# CPU_ROM.net
KiCad netlist of a schematic drawn in Altium Designer
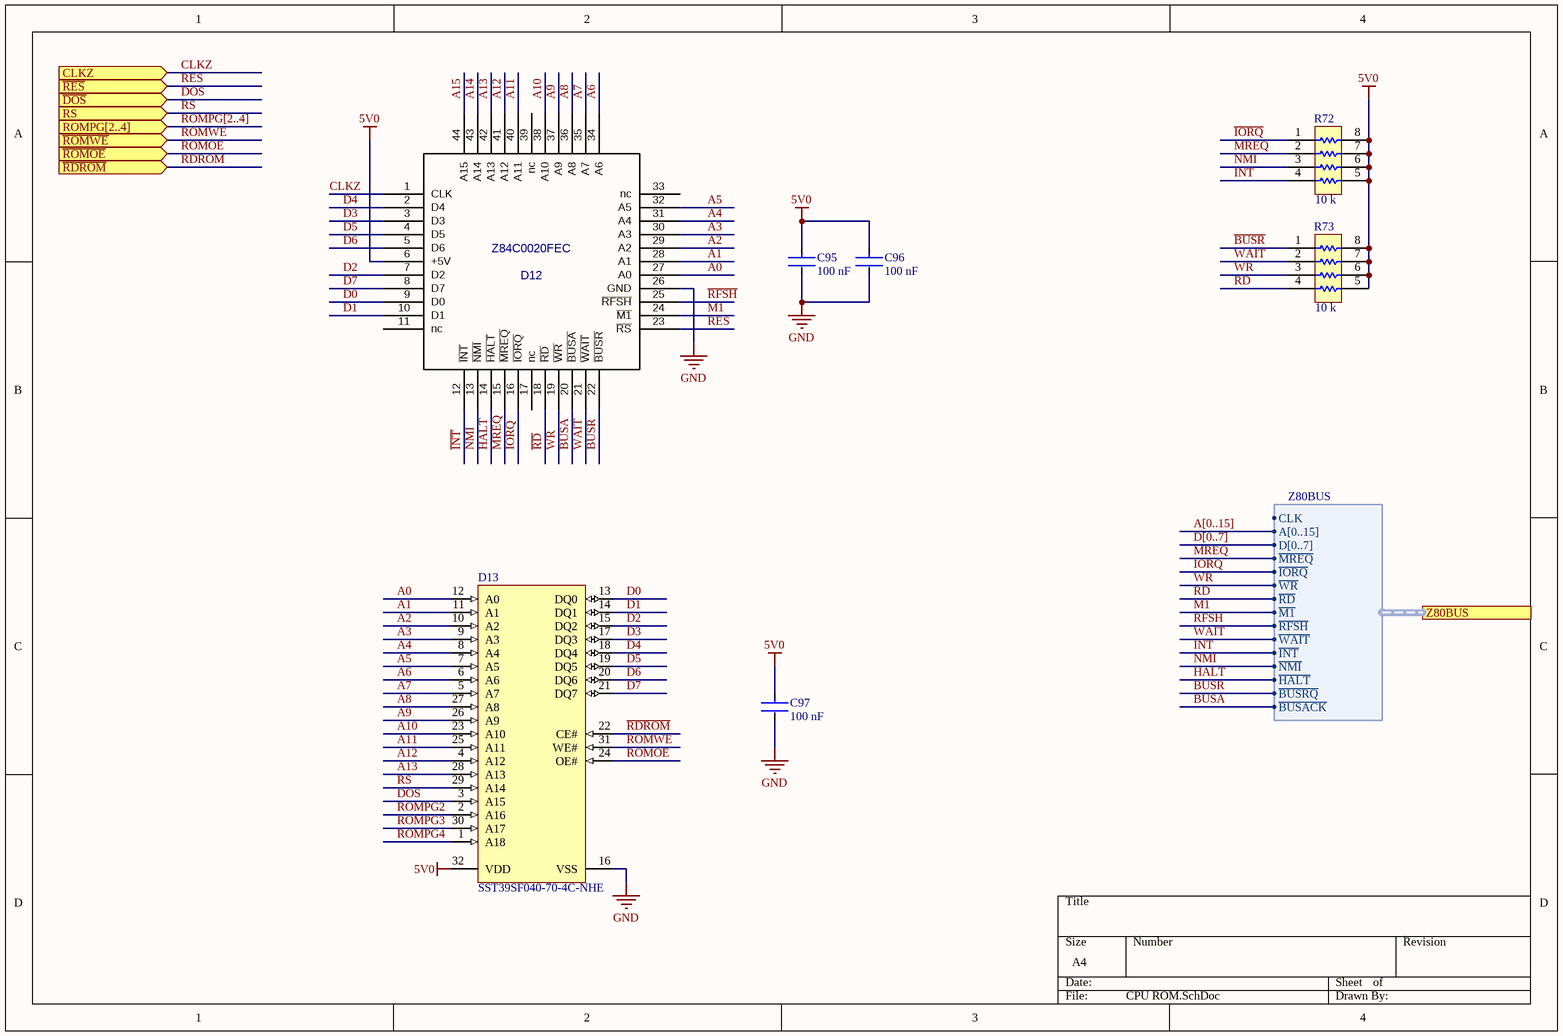
[diagram p0: CPU ROM.SchDoc]

(export (version "E")
  (design (tool "Eeschema 10.0.6"))
  (components
    (comp (ref "C95")
      (value "CC0805-1.5pF")
      (footprint "CC0805")
      (description "CL21 Series 0805 1.5pF 50V ±0.25pF Tolerance C0G Multilayer Ceramic Chip Capacitor")
      (fields
        (field (name "MANUFACTURER PART NUMBER") "CL21C1R5CBANNNC")
        (field (name "CAPACITANCE") "100 nF")
        (field (name "MANUFACTURER") "Samsung")
      )
      (libsource (lib "zxevo") (part "CC0805"))
    )
    (comp (ref "C96")
      (value "CC0805-1.5pF")
      (footprint "CC0805")
      (description "CL21 Series 0805 1.5pF 50V ±0.25pF Tolerance C0G Multilayer Ceramic Chip Capacitor")
      (fields
        (field (name "MANUFACTURER PART NUMBER") "CL21C1R5CBANNNC")
        (field (name "CAPACITANCE") "100 nF")
        (field (name "MANUFACTURER") "Samsung")
      )
      (libsource (lib "zxevo") (part "CC0805"))
    )
    (comp (ref "C97")
      (value "CC0805-1.5pF")
      (footprint "CC0805")
      (description "CL21 Series 0805 1.5pF 50V ±0.25pF Tolerance C0G Multilayer Ceramic Chip Capacitor")
      (fields
        (field (name "MANUFACTURER PART NUMBER") "CL21C1R5CBANNNC")
        (field (name "CAPACITANCE") "100 nF")
        (field (name "MANUFACTURER") "Samsung")
      )
      (libsource (lib "zxevo") (part "CC0805"))
    )
    (comp (ref "D12")
      (value "Z84C0020FEC")
      (footprint "QFP44X8")
      (libsource (lib "zxevo") (part "Z84C0020FEC"))
    )
    (comp (ref "D13")
      (value "SST39SF040-70-4C-NHE")
      (footprint "MCHP-PLCC-NH32_L")
      (description "4 Mbit Multi-Purpose Flash, 4.5 to 5.5 V, 1 kHz, 0 to 70 degC, 32-pin PLCC (NH32), Tube")
      (fields (field (name "MANUFACTURER") "Microchip"))
      (libsource (lib "zxevo") (part "SST39SF040-70-4C-NHE"))
    )
    (comp (ref "R72")
      (value "CAY16-103J4LF")
      (footprint "BOUR-CAY16-J4_V")
      (description "Chip Resistor Array, 10 KOhm, +/- 5%, 62.5 mW, -55 to 125 degC, 8-Pin SMD, RoHS, Tape and Reel")
      (fields (field (name "TOLERANCE") "1%") (field (name "RESISTANCE") "10 k"))
      (libsource (lib "Altium Content Vault") (part "RES-P-8"))
    )
    (comp (ref "R73")
      (value "CAY16-103J4LF")
      (footprint "BOUR-CAY16-J4_V")
      (description "Chip Resistor Array, 10 KOhm, +/- 5%, 62.5 mW, -55 to 125 degC, 8-Pin SMD, RoHS, Tape and Reel")
      (fields (field (name "TOLERANCE") "1%") (field (name "RESISTANCE") "10 k"))
      (libsource (lib "Altium Content Vault") (part "RES-P-8"))
    )
  )
  (nets
    (net (code "2") (name "/A0") (class "Default")
      (node (ref "D12") (pin "27") (pinfunction "A0_27") (pintype "passive"))
      (node (ref "D13") (pin "12") (pinfunction "A0_12") (pintype "input"))
    )
    (net (code "3") (name "/A1") (class "Default")
      (node (ref "D12") (pin "28") (pinfunction "A1_28") (pintype "passive"))
      (node (ref "D13") (pin "11") (pinfunction "A1_11") (pintype "input"))
    )
    (net (code "4") (name "/A2") (class "Default")
      (node (ref "D12") (pin "29") (pinfunction "A2_29") (pintype "passive"))
      (node (ref "D13") (pin "10") (pinfunction "A2_10") (pintype "input"))
    )
    (net (code "5") (name "/A3") (class "Default")
      (node (ref "D12") (pin "30") (pinfunction "A3_30") (pintype "passive"))
      (node (ref "D13") (pin "9") (pinfunction "A3_9") (pintype "input"))
    )
    (net (code "6") (name "/A4") (class "Default")
      (node (ref "D12") (pin "31") (pinfunction "A4_31") (pintype "passive"))
      (node (ref "D13") (pin "8") (pinfunction "A4_8") (pintype "input"))
    )
    (net (code "7") (name "/A5") (class "Default")
      (node (ref "D12") (pin "32") (pinfunction "A5_32") (pintype "passive"))
      (node (ref "D13") (pin "7") (pinfunction "A5_7") (pintype "input"))
    )
    (net (code "8") (name "/A6") (class "Default")
      (node (ref "D12") (pin "34") (pinfunction "A6_34") (pintype "passive"))
      (node (ref "D13") (pin "6") (pinfunction "A6_6") (pintype "input"))
    )
    (net (code "9") (name "/A7") (class "Default")
      (node (ref "D12") (pin "35") (pinfunction "A7_35") (pintype "passive"))
      (node (ref "D13") (pin "5") (pinfunction "A7_5") (pintype "input"))
    )
    (net (code "10") (name "/A8") (class "Default")
      (node (ref "D12") (pin "36") (pinfunction "A8_36") (pintype "passive"))
      (node (ref "D13") (pin "27") (pinfunction "A8_27") (pintype "input"))
    )
    (net (code "11") (name "/A9") (class "Default")
      (node (ref "D12") (pin "37") (pinfunction "A9_37") (pintype "passive"))
      (node (ref "D13") (pin "26") (pinfunction "A9_26") (pintype "input"))
    )
    (net (code "12") (name "/A10") (class "Default")
      (node (ref "D12") (pin "38") (pinfunction "A10_38") (pintype "passive"))
      (node (ref "D13") (pin "23") (pinfunction "A10_23") (pintype "input"))
    )
    (net (code "13") (name "/A11") (class "Default")
      (node (ref "D12") (pin "40") (pinfunction "A11_40") (pintype "passive"))
      (node (ref "D13") (pin "25") (pinfunction "A11_25") (pintype "input"))
    )
    (net (code "14") (name "/A12") (class "Default")
      (node (ref "D12") (pin "41") (pinfunction "A12_41") (pintype "passive"))
      (node (ref "D13") (pin "4") (pinfunction "A12_4") (pintype "input"))
    )
    (net (code "15") (name "/A13") (class "Default")
      (node (ref "D12") (pin "42") (pinfunction "A13_42") (pintype "passive"))
      (node (ref "D13") (pin "28") (pinfunction "A13_28") (pintype "input"))
    )
    (net (code "16") (name "/A14") (class "Default")
      (node (ref "D12") (pin "43") (pinfunction "A14_43") (pintype "passive"))
    )
    (net (code "17") (name "/A15") (class "Default")
      (node (ref "D12") (pin "44") (pinfunction "A15_44") (pintype "passive"))
    )
    (net (code "18") (name "/CLKZ") (class "Default")
      (node (ref "D12") (pin "1") (pinfunction "CLK_1") (pintype "passive"))
    )
    (net (code "19") (name "/D0") (class "Default")
      (node (ref "D12") (pin "9") (pinfunction "D0_9") (pintype "passive"))
      (node (ref "D13") (pin "13") (pinfunction "DQ0_13") (pintype "bidirectional"))
    )
    (net (code "20") (name "/D1") (class "Default")
      (node (ref "D12") (pin "10") (pinfunction "D1_10") (pintype "passive"))
      (node (ref "D13") (pin "14") (pinfunction "DQ1_14") (pintype "bidirectional"))
    )
    (net (code "21") (name "/D2") (class "Default")
      (node (ref "D12") (pin "7") (pinfunction "D2_7") (pintype "passive"))
      (node (ref "D13") (pin "15") (pinfunction "DQ2_15") (pintype "bidirectional"))
    )
    (net (code "22") (name "/D3") (class "Default")
      (node (ref "D12") (pin "3") (pinfunction "D3_3") (pintype "passive"))
      (node (ref "D13") (pin "17") (pinfunction "DQ3_17") (pintype "bidirectional"))
    )
    (net (code "23") (name "/D4") (class "Default")
      (node (ref "D12") (pin "2") (pinfunction "D4_2") (pintype "passive"))
      (node (ref "D13") (pin "18") (pinfunction "DQ4_18") (pintype "bidirectional"))
    )
    (net (code "24") (name "/D5") (class "Default")
      (node (ref "D12") (pin "4") (pinfunction "D5_4") (pintype "passive"))
      (node (ref "D13") (pin "19") (pinfunction "DQ5_19") (pintype "bidirectional"))
    )
    (net (code "25") (name "/D6") (class "Default")
      (node (ref "D12") (pin "5") (pinfunction "D6_5") (pintype "passive"))
      (node (ref "D13") (pin "20") (pinfunction "DQ6_20") (pintype "bidirectional"))
    )
    (net (code "26") (name "/D7") (class "Default")
      (node (ref "D12") (pin "8") (pinfunction "D7_8") (pintype "passive"))
      (node (ref "D13") (pin "21") (pinfunction "DQ7_21") (pintype "bidirectional"))
    )
    (net (code "28") (name "/ROMPG2") (class "Default")
      (node (ref "D13") (pin "2") (pinfunction "A16_2") (pintype "input"))
    )
    (net (code "29") (name "/ROMPG3") (class "Default")
      (node (ref "D13") (pin "30") (pinfunction "A17_30") (pintype "input"))
    )
    (net (code "30") (name "/ROMPG4") (class "Default")
      (node (ref "D13") (pin "1") (pinfunction "A18_1") (pintype "input"))
    )
    (net (code "32") (name "/RS") (class "Default")
      (node (ref "D13") (pin "29") (pinfunction "A14_29") (pintype "input"))
    )
    (net (code "35") (name "/~{BUSA}") (class "Default")
      (node (ref "D12") (pin "20") (pinfunction "~{BUSA}_20") (pintype "passive"))
    )
    (net (code "36") (name "/~{BUSR}") (class "Default")
      (node (ref "D12") (pin "22") (pinfunction "~{BUSR}_22") (pintype "passive"))
      (node (ref "R73") (pin "1") (pinfunction "1_1") (pintype "passive"))
    )
    (net (code "37") (name "/~{DOS}") (class "Default")
      (node (ref "D13") (pin "3") (pinfunction "A15_3") (pintype "input"))
    )
    (net (code "38") (name "/~{HALT}") (class "Default")
      (node (ref "D12") (pin "14") (pinfunction "~{HALT}_14") (pintype "passive"))
    )
    (net (code "39") (name "/~{INT}") (class "Default")
      (node (ref "D12") (pin "12") (pinfunction "~{INT}_12") (pintype "passive"))
      (node (ref "R72") (pin "4") (pinfunction "4_4") (pintype "passive"))
    )
    (net (code "40") (name "/~{IORQ}") (class "Default")
      (node (ref "D12") (pin "16") (pinfunction "~{IORQ}_16") (pintype "passive"))
      (node (ref "R72") (pin "1") (pinfunction "1_1") (pintype "passive"))
    )
    (net (code "41") (name "/~{M1}") (class "Default")
      (node (ref "D12") (pin "24") (pinfunction "~{M1}_24") (pintype "passive"))
    )
    (net (code "42") (name "/~{MREQ}") (class "Default")
      (node (ref "D12") (pin "15") (pinfunction "~{MREQ}_15") (pintype "passive"))
      (node (ref "R72") (pin "2") (pinfunction "2_2") (pintype "passive"))
    )
    (net (code "43") (name "/~{NMI}") (class "Default")
      (node (ref "D12") (pin "13") (pinfunction "~{NMI}_13") (pintype "passive"))
      (node (ref "R72") (pin "3") (pinfunction "3_3") (pintype "passive"))
    )
    (net (code "44") (name "/~{RDROM}") (class "Default")
      (node (ref "D13") (pin "22") (pinfunction "CE#_22") (pintype "input"))
    )
    (net (code "45") (name "/~{RD}") (class "Default")
      (node (ref "D12") (pin "18") (pinfunction "~{RD}_18") (pintype "passive"))
      (node (ref "R73") (pin "4") (pinfunction "4_4") (pintype "passive"))
    )
    (net (code "46") (name "/~{RES}") (class "Default")
      (node (ref "D12") (pin "23") (pinfunction "~{RS}_23") (pintype "passive"))
    )
    (net (code "47") (name "/~{RFSH}") (class "Default")
      (node (ref "D12") (pin "25") (pinfunction "~{RFSH}_25") (pintype "passive"))
    )
    (net (code "48") (name "/~{ROMOE}") (class "Default")
      (node (ref "D13") (pin "24") (pinfunction "OE#_24") (pintype "input"))
    )
    (net (code "49") (name "/~{ROMWE}") (class "Default")
      (node (ref "D13") (pin "31") (pinfunction "WE#_31") (pintype "input"))
    )
    (net (code "50") (name "/~{WAIT}") (class "Default")
      (node (ref "D12") (pin "21") (pinfunction "~{WAIT}_21") (pintype "passive"))
      (node (ref "R73") (pin "2") (pinfunction "2_2") (pintype "passive"))
    )
    (net (code "51") (name "/~{WR}") (class "Default")
      (node (ref "D12") (pin "19") (pinfunction "~{WR}_19") (pintype "passive"))
      (node (ref "R73") (pin "3") (pinfunction "3_3") (pintype "passive"))
    )
    (net (code "52") (name "5V0") (class "Default")
      (node (ref "C95") (pin "1") (pinfunction "1_1") (pintype "passive"))
      (node (ref "C96") (pin "1") (pinfunction "1_1") (pintype "passive"))
      (node (ref "C97") (pin "1") (pinfunction "1_1") (pintype "passive"))
      (node (ref "D12") (pin "6") (pinfunction "+5V_6") (pintype "passive"))
      (node (ref "D13") (pin "32") (pinfunction "VDD_32") (pintype "power_in"))
      (node (ref "R72") (pin "5") (pinfunction "5_5") (pintype "passive"))
      (node (ref "R72") (pin "6") (pinfunction "6_6") (pintype "passive"))
      (node (ref "R72") (pin "7") (pinfunction "7_7") (pintype "passive"))
      (node (ref "R72") (pin "8") (pinfunction "8_8") (pintype "passive"))
      (node (ref "R73") (pin "5") (pinfunction "5_5") (pintype "passive"))
      (node (ref "R73") (pin "6") (pinfunction "6_6") (pintype "passive"))
      (node (ref "R73") (pin "7") (pinfunction "7_7") (pintype "passive"))
      (node (ref "R73") (pin "8") (pinfunction "8_8") (pintype "passive"))
    )
    (net (code "53") (name "GND") (class "Default")
      (node (ref "C95") (pin "2") (pinfunction "2_2") (pintype "passive"))
      (node (ref "C96") (pin "2") (pinfunction "2_2") (pintype "passive"))
      (node (ref "C97") (pin "2") (pinfunction "2_2") (pintype "passive"))
      (node (ref "D12") (pin "26") (pinfunction "GND_26") (pintype "passive"))
      (node (ref "D13") (pin "16") (pinfunction "VSS_16") (pintype "power_in"))
    )
    (net (code "54") (name "unconnected-(D12-nc-Pad11)") (class "Default")
      (node (ref "D12") (pin "11") (pinfunction "nc_11") (pintype "passive"))
    )
    (net (code "55") (name "unconnected-(D12-nc-Pad17)") (class "Default")
      (node (ref "D12") (pin "17") (pinfunction "nc_17") (pintype "passive"))
    )
    (net (code "56") (name "unconnected-(D12-nc-Pad33)") (class "Default")
      (node (ref "D12") (pin "33") (pinfunction "nc_33") (pintype "passive"))
    )
    (net (code "57") (name "unconnected-(D12-nc-Pad39)") (class "Default")
      (node (ref "D12") (pin "39") (pinfunction "nc_39") (pintype "passive"))
    )
  )
)
